# STM32_microcontroller_IOs.net
KiCad netlist of a schematic drawn in Altium Designer
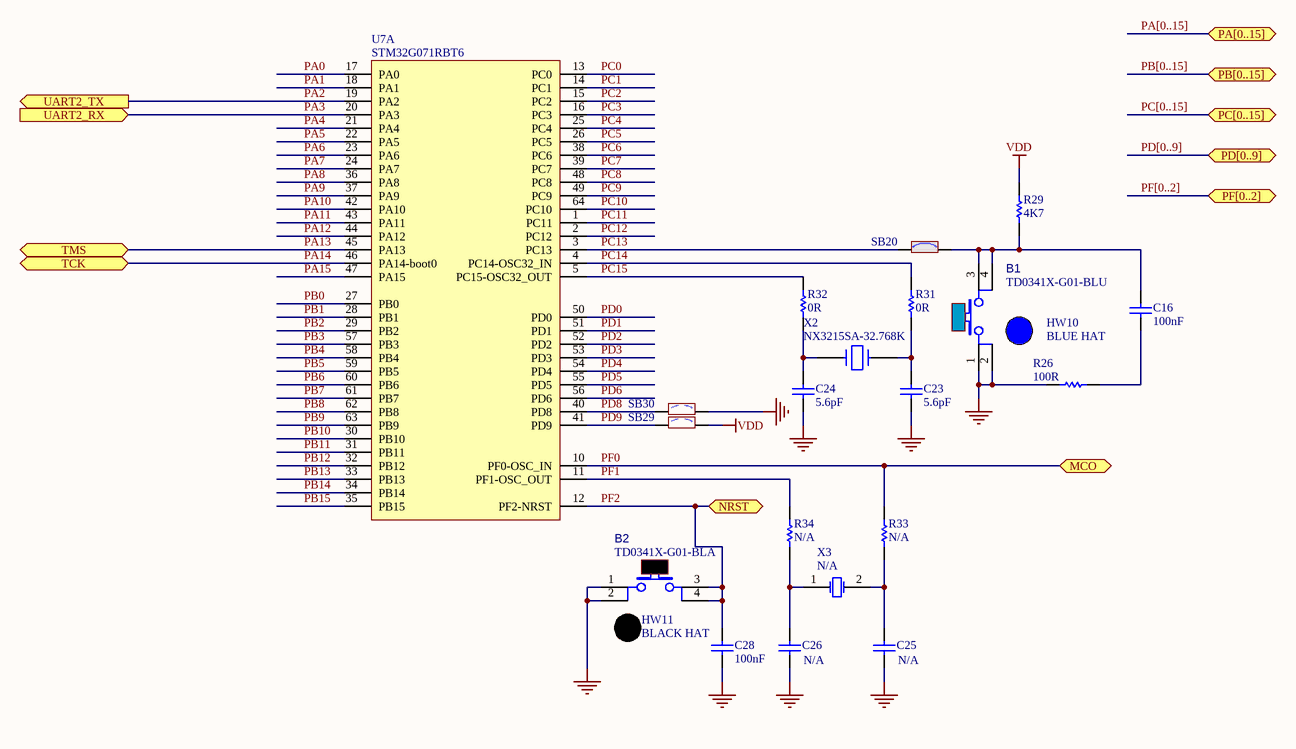
[diagram p0: STM32_microcontroller_IOs.SchDoc]

(export (version "E")
  (design (tool "Eeschema 10.0.6"))
  (components
    (comp (ref "B1")
      (value "SW-PUSH-CMS_BLUE")
      (footprint "SWI_WEALTHMETAL_TD-0341_4P_BLUE")
      (description "Non-Open Push-Button 0.1A 24V")
      (fields
        (field (name "INTERNAL_PART_NUMBER") "MCD-00002")
        (field (name "MANUFACTURER_PART_NUMBER") "TD0341X-G01-BLU")
        (field (name "MANUFACTURER") "WEALTHMETAL")
        (field (name "PROVIDED_BY") "Subcon")
      )
      (libsource (lib "MCD_PARTS_database") (part "SW-PUSH-CMS_BLUE"))
    )
    (comp (ref "B2")
      (value "SW-PUSH-CMS_BLACK")
      (footprint "SWI_WEALTHMETAL_TD-0341_4P_BLACK")
      (description "Non-Open Push-Button 0.1A 24V")
      (fields
        (field (name "INTERNAL_PART_NUMBER") "MCD-00001")
        (field (name "MANUFACTURER_PART_NUMBER") "TD0341X-G01-BLA")
        (field (name "MANUFACTURER") "WEALTHMETAL")
        (field (name "PROVIDED_BY") "Subcon")
      )
      (libsource (lib "MCD_PARTS_database") (part "SW-PUSH-CMS_BLACK"))
    )
    (comp (ref "C16")
      (value "100nF")
      (footprint "C0603")
      (description "Capacitor, MLCC, 100nF, 16V, X7R, 10%, 0603, T=0,8mm")
      (fields
        (field (name "INTERNAL_PART_NUMBER") "MCD-00211")
        (field (name "MANUFACTURER_PART_NUMBER") "CC0603KRX7R7BB104")
        (field (name "PROVIDED_BY") "Subcon")
      )
      (libsource (lib "MCD_PARTS_database") (part "Capacitor"))
    )
    (comp (ref "C23")
      (value "5.6pF")
      (footprint "C0603")
      (description "Capacitor,5.6pF,0.1pF,16V,NPO,0603")
      (fields
        (field (name "INTERNAL_PART_NUMBER") "MCD-00666")
        (field (name "MANUFACTURER_PART_NUMBER") "CC0603BRNPO7BN5R6")
        (field (name "PROVIDED_BY") "Subcon")
      )
      (libsource (lib "MCD_PARTS_database") (part "Capacitor"))
    )
    (comp (ref "C24")
      (value "5.6pF")
      (footprint "C0603")
      (description "Capacitor,5.6pF,0.1pF,16V,NPO,0603")
      (fields
        (field (name "INTERNAL_PART_NUMBER") "MCD-00666")
        (field (name "MANUFACTURER_PART_NUMBER") "CC0603BRNPO7BN5R6")
        (field (name "PROVIDED_BY") "Subcon")
      )
      (libsource (lib "MCD_PARTS_database") (part "Capacitor"))
    )
    (comp (ref "C25")
      (value "N/A")
      (footprint "C0603")
      (description "Capacitor, MLCC, 10pF, 50V, NPO, 5%, 0603, T=0,8mm")
      (fields
        (field (name "INTERNAL_PART_NUMBER") "MCD-00637")
        (field (name "MANUFACTURER_PART_NUMBER") "CC0603JRNPO9BN100")
        (field (name "PROVIDED_BY") "subcon")
      )
      (libsource (lib "MCD_PARTS_database") (part "Capacitor"))
    )
    (comp (ref "C26")
      (value "N/A")
      (footprint "C0603")
      (description "Capacitor, MLCC, 10pF, 50V, NPO, 5%, 0603, T=0,8mm")
      (fields
        (field (name "INTERNAL_PART_NUMBER") "MCD-00637")
        (field (name "MANUFACTURER_PART_NUMBER") "CC0603JRNPO9BN100")
        (field (name "PROVIDED_BY") "subcon")
      )
      (libsource (lib "MCD_PARTS_database") (part "Capacitor"))
    )
    (comp (ref "C28")
      (value "100nF")
      (footprint "C0603")
      (description "Capacitor, MLCC, 100nF, 16V, X7R, 10%, 0603, T=0,8mm")
      (fields
        (field (name "INTERNAL_PART_NUMBER") "MCD-00211")
        (field (name "MANUFACTURER_PART_NUMBER") "CC0603KRX7R7BB104")
        (field (name "PROVIDED_BY") "Subcon")
      )
      (libsource (lib "MCD_PARTS_database") (part "Capacitor"))
    )
    (comp (ref "HW10")
      (value "BLUE HAT")
      (description "Blue Hat for switch TD0341X-G01-BLU")
      (fields
        (field (name "INTERNAL_PART_NUMBER") "MCD-00634")
        (field (name "MANUFACTURER_PART_NUMBER") "988.16.09.3.00002_SH-517")
        (field (name "PROVIDED_BY") "Subcon")
      )
      (libsource (lib "MCD_PARTS_database") (part "BUTTON_HAT_BLUE"))
    )
    (comp (ref "HW11")
      (value "BLACK HAT")
      (description "Black Hat for switch TD0341X-G01-BLA")
      (fields
        (field (name "INTERNAL_PART_NUMBER") "MCD-00635")
        (field (name "MANUFACTURER_PART_NUMBER") "988.16.09.3.00003_SH-517")
        (field (name "PROVIDED_BY") "Subcon")
      )
      (libsource (lib "MCD_PARTS_database") (part "BUTTON_HAT_BLACK"))
    )
    (comp (ref "R26")
      (value "100R")
      (footprint "R0603")
      (description "Resistor,100R,0603,1%,1/10W")
      (fields
        (field (name "INTERNAL_PART_NUMBER") "MCD-00224")
        (field (name "MANUFACTURER_PART_NUMBER") "RC0603FR-07100RL")
        (field (name "PROVIDED_BY") "Subcon")
      )
      (libsource (lib "MCD_PARTS_database") (part "Resistor"))
    )
    (comp (ref "R29")
      (value "4K7")
      (footprint "R0603")
      (description "Resistor,4K7,0603,1%,1/10W")
      (fields
        (field (name "INTERNAL_PART_NUMBER") "MCD-00219")
        (field (name "MANUFACTURER_PART_NUMBER") "RC0603FR-074K7L")
        (field (name "PROVIDED_BY") "Subcon")
      )
      (libsource (lib "MCD_PARTS_database") (part "Resistor"))
    )
    (comp (ref "R31")
      (value "0R")
      (footprint "R0603")
      (description "Resistor,0R,0603,ULO")
      (fields
        (field (name "INTERNAL_PART_NUMBER") "MCD-00181")
        (field (name "MANUFACTURER_PART_NUMBER") "PMR03EZPJ000")
        (field (name "PROVIDED_BY") "Subcon")
      )
      (libsource (lib "MCD_PARTS_database") (part "Resistor"))
    )
    (comp (ref "R32")
      (value "0R")
      (footprint "R0603")
      (description "Resistor,0R,0603,ULO")
      (fields
        (field (name "INTERNAL_PART_NUMBER") "MCD-00181")
        (field (name "MANUFACTURER_PART_NUMBER") "PMR03EZPJ000")
        (field (name "PROVIDED_BY") "Subcon")
      )
      (libsource (lib "MCD_PARTS_database") (part "Resistor"))
    )
    (comp (ref "R33")
      (value "N/A")
      (footprint "R0603")
      (description "Resistor,100R,0603,1%,1/10W")
      (fields
        (field (name "INTERNAL_PART_NUMBER") "MCD-00224")
        (field (name "MANUFACTURER_PART_NUMBER") "RC0603FR-07100RL")
        (field (name "PROVIDED_BY") "Subcon")
      )
      (libsource (lib "MCD_PARTS_database") (part "Resistor"))
    )
    (comp (ref "R34")
      (value "N/A")
      (footprint "R0603")
      (description "Resistor,100R,0603,1%,1/10W")
      (fields
        (field (name "INTERNAL_PART_NUMBER") "MCD-00224")
        (field (name "MANUFACTURER_PART_NUMBER") "RC0603FR-07100RL")
        (field (name "PROVIDED_BY") "Subcon")
      )
      (libsource (lib "MCD_PARTS_database") (part "Resistor"))
    )
    (comp (ref "SB20")
      (value "SB_ON")
      (footprint "SOLDER-BRIDGE_R0603-0R")
      (description "Solder Bridge ON")
      (fields (field (name "INTERNAL_PART_NUMBER") "MCD-00071") (field (name "PROVIDED_BY") "Subcon"))
      (libsource (lib "MCD_PARTS_database") (part "SB_ON"))
    )
    (comp (ref "SB29")
      (value "SB_OFF")
      (footprint "SOLDER-BRIDGE_R0603-0R")
      (description "Solder Bridge OFF")
      (fields (field (name "INTERNAL_PART_NUMBER") "MCD-00072"))
      (libsource (lib "MCD_PARTS_database") (part "SB_OFF"))
    )
    (comp (ref "SB30")
      (value "SB_OFF")
      (footprint "SOLDER-BRIDGE_R0603-0R")
      (description "Solder Bridge OFF")
      (fields (field (name "INTERNAL_PART_NUMBER") "MCD-00072"))
      (libsource (lib "MCD_PARTS_database") (part "SB_OFF"))
    )
    (comp (ref "U7")
      (value "STM32G071RBT6")
      (footprint "ICC_LQFP64_10X10_P050_SOCKET_YAMAICHI_IC149-064-069-B5")
      (description "Medium-density performance line ARM-based 32-bit MCU with 128KB Flash")
      (fields
        (field (name "INTERNAL_PART_NUMBER") "MCD-00662")
        (field (name "MANUFACTURER") "STMICROELECTRONICS")
        (field (name "PROVIDED_BY") "STM")
      )
      (libsource (lib "MCD_PARTS_database") (part "STM32G071RBT6"))
    )
    (comp (ref "X2")
      (value "NX3215SA-32.768K")
      (footprint "CRY_NX3215SA_2P")
      (description "Crystal 32.768kHz, 6pF, -+20PPM, R=50K, SMD")
      (fields
        (field (name "INTERNAL_PART_NUMBER") "MCD-00091")
        (field (name "MANUFACTURER_PART_NUMBER") "NX3215SA 32.768KHz EXS00A-MU00525")
        (field (name "PROVIDED_BY") "STM")
      )
      (libsource (lib "MCD_PARTS_database") (part "XTAL_32K_NX3215SA"))
    )
    (comp (ref "X3")
      (value "N/A")
      (footprint "CRY_NX3225GD_2P")
      (description "Crystal 8Mhz, 8pF, -+50PPM, SMD")
      (fields
        (field (name "INTERNAL_PART_NUMBER") "MCD-00092")
        (field (name "MANUFACTURER_PART_NUMBER") "NX3225GD 8MHz EXS00A-CG04874")
        (field (name "PROVIDED_BY") "STM")
      )
      (libsource (lib "MCD_PARTS_database") (part "XTAL_8M_NX3225GD"))
    )
  )
  (nets
    (net (code "2") (name "/PA0") (class "Default")
      (node (ref "U7") (pin "17") (pinfunction "PA0_17") (pintype "passive"))
    )
    (net (code "3") (name "/PA1") (class "Default")
      (node (ref "U7") (pin "18") (pinfunction "PA1_18") (pintype "passive"))
    )
    (net (code "4") (name "/PA2") (class "Default")
      (node (ref "U7") (pin "19") (pinfunction "PA2_19") (pintype "passive"))
    )
    (net (code "5") (name "/PA3") (class "Default")
      (node (ref "U7") (pin "20") (pinfunction "PA3_20") (pintype "passive"))
    )
    (net (code "6") (name "/PA4") (class "Default")
      (node (ref "U7") (pin "21") (pinfunction "PA4_21") (pintype "passive"))
    )
    (net (code "7") (name "/PA5") (class "Default")
      (node (ref "U7") (pin "22") (pinfunction "PA5_22") (pintype "passive"))
    )
    (net (code "8") (name "/PA6") (class "Default")
      (node (ref "U7") (pin "23") (pinfunction "PA6_23") (pintype "passive"))
    )
    (net (code "9") (name "/PA7") (class "Default")
      (node (ref "U7") (pin "24") (pinfunction "PA7_24") (pintype "passive"))
    )
    (net (code "10") (name "/PA8") (class "Default")
      (node (ref "U7") (pin "36") (pinfunction "PA8_36") (pintype "passive"))
    )
    (net (code "11") (name "/PA9") (class "Default")
      (node (ref "U7") (pin "37") (pinfunction "PA9_37") (pintype "passive"))
    )
    (net (code "12") (name "/PA10") (class "Default")
      (node (ref "U7") (pin "42") (pinfunction "PA10_42") (pintype "passive"))
    )
    (net (code "13") (name "/PA11") (class "Default")
      (node (ref "U7") (pin "43") (pinfunction "PA11_43") (pintype "passive"))
    )
    (net (code "14") (name "/PA12") (class "Default")
      (node (ref "U7") (pin "44") (pinfunction "PA12_44") (pintype "passive"))
    )
    (net (code "15") (name "/PA13") (class "Default")
      (node (ref "U7") (pin "45") (pinfunction "PA13_45") (pintype "passive"))
    )
    (net (code "16") (name "/PA14") (class "Default")
      (node (ref "U7") (pin "46") (pinfunction "PA14-boot0_46") (pintype "passive"))
    )
    (net (code "17") (name "/PA15") (class "Default")
      (node (ref "U7") (pin "47") (pinfunction "PA15_47") (pintype "passive"))
    )
    (net (code "19") (name "/PB0") (class "Default")
      (node (ref "U7") (pin "27") (pinfunction "PB0_27") (pintype "passive"))
    )
    (net (code "20") (name "/PB1") (class "Default")
      (node (ref "U7") (pin "28") (pinfunction "PB1_28") (pintype "passive"))
    )
    (net (code "21") (name "/PB2") (class "Default")
      (node (ref "U7") (pin "29") (pinfunction "PB2_29") (pintype "passive"))
    )
    (net (code "22") (name "/PB3") (class "Default")
      (node (ref "U7") (pin "57") (pinfunction "PB3_57") (pintype "passive"))
    )
    (net (code "23") (name "/PB4") (class "Default")
      (node (ref "U7") (pin "58") (pinfunction "PB4_58") (pintype "passive"))
    )
    (net (code "24") (name "/PB5") (class "Default")
      (node (ref "U7") (pin "59") (pinfunction "PB5_59") (pintype "passive"))
    )
    (net (code "25") (name "/PB6") (class "Default")
      (node (ref "U7") (pin "60") (pinfunction "PB6_60") (pintype "passive"))
    )
    (net (code "26") (name "/PB7") (class "Default")
      (node (ref "U7") (pin "61") (pinfunction "PB7_61") (pintype "passive"))
    )
    (net (code "27") (name "/PB8") (class "Default")
      (node (ref "U7") (pin "62") (pinfunction "PB8_62") (pintype "passive"))
    )
    (net (code "28") (name "/PB9") (class "Default")
      (node (ref "U7") (pin "63") (pinfunction "PB9_63") (pintype "passive"))
    )
    (net (code "29") (name "/PB10") (class "Default")
      (node (ref "U7") (pin "30") (pinfunction "PB10_30") (pintype "passive"))
    )
    (net (code "30") (name "/PB11") (class "Default")
      (node (ref "U7") (pin "31") (pinfunction "PB11_31") (pintype "passive"))
    )
    (net (code "31") (name "/PB12") (class "Default")
      (node (ref "U7") (pin "32") (pinfunction "PB12_32") (pintype "passive"))
    )
    (net (code "32") (name "/PB13") (class "Default")
      (node (ref "U7") (pin "33") (pinfunction "PB13_33") (pintype "passive"))
    )
    (net (code "33") (name "/PB14") (class "Default")
      (node (ref "U7") (pin "34") (pinfunction "PB14_34") (pintype "passive"))
    )
    (net (code "34") (name "/PB15") (class "Default")
      (node (ref "U7") (pin "35") (pinfunction "PB15_35") (pintype "passive"))
    )
    (net (code "36") (name "/PC0") (class "Default")
      (node (ref "U7") (pin "13") (pinfunction "PC0_13") (pintype "passive"))
    )
    (net (code "37") (name "/PC1") (class "Default")
      (node (ref "U7") (pin "14") (pinfunction "PC1_14") (pintype "passive"))
    )
    (net (code "38") (name "/PC2") (class "Default")
      (node (ref "U7") (pin "15") (pinfunction "PC2_15") (pintype "passive"))
    )
    (net (code "39") (name "/PC3") (class "Default")
      (node (ref "U7") (pin "16") (pinfunction "PC3_16") (pintype "passive"))
    )
    (net (code "40") (name "/PC4") (class "Default")
      (node (ref "U7") (pin "25") (pinfunction "PC4_25") (pintype "passive"))
    )
    (net (code "41") (name "/PC5") (class "Default")
      (node (ref "U7") (pin "26") (pinfunction "PC5_26") (pintype "passive"))
    )
    (net (code "42") (name "/PC6") (class "Default")
      (node (ref "U7") (pin "38") (pinfunction "PC6_38") (pintype "passive"))
    )
    (net (code "43") (name "/PC7") (class "Default")
      (node (ref "U7") (pin "39") (pinfunction "PC7_39") (pintype "passive"))
    )
    (net (code "44") (name "/PC8") (class "Default")
      (node (ref "U7") (pin "48") (pinfunction "PC8_48") (pintype "passive"))
    )
    (net (code "45") (name "/PC9") (class "Default")
      (node (ref "U7") (pin "49") (pinfunction "PC9_49") (pintype "passive"))
    )
    (net (code "46") (name "/PC10") (class "Default")
      (node (ref "U7") (pin "64") (pinfunction "PC10_64") (pintype "passive"))
    )
    (net (code "47") (name "/PC11") (class "Default")
      (node (ref "U7") (pin "1") (pinfunction "PC11_1") (pintype "passive"))
    )
    (net (code "48") (name "/PC12") (class "Default")
      (node (ref "U7") (pin "2") (pinfunction "PC12_2") (pintype "passive"))
    )
    (net (code "49") (name "/PC13") (class "Default")
      (node (ref "SB20") (pin "1") (pinfunction "1_1") (pintype "passive"))
      (node (ref "U7") (pin "3") (pinfunction "PC13_3") (pintype "passive"))
    )
    (net (code "50") (name "/PC14") (class "Default")
      (node (ref "R31") (pin "1") (pinfunction "1_1") (pintype "passive"))
      (node (ref "U7") (pin "4") (pinfunction "PC14-OSC32_IN_4") (pintype "passive"))
    )
    (net (code "51") (name "/PC15") (class "Default")
      (node (ref "R32") (pin "1") (pinfunction "1_1") (pintype "passive"))
      (node (ref "U7") (pin "5") (pinfunction "PC15-OSC32_OUT_5") (pintype "passive"))
    )
    (net (code "53") (name "/PD0") (class "Default")
      (node (ref "U7") (pin "50") (pinfunction "PD0_50") (pintype "passive"))
    )
    (net (code "54") (name "/PD1") (class "Default")
      (node (ref "U7") (pin "51") (pinfunction "PD1_51") (pintype "passive"))
    )
    (net (code "55") (name "/PD2") (class "Default")
      (node (ref "U7") (pin "52") (pinfunction "PD2_52") (pintype "passive"))
    )
    (net (code "56") (name "/PD3") (class "Default")
      (node (ref "U7") (pin "53") (pinfunction "PD3_53") (pintype "passive"))
    )
    (net (code "57") (name "/PD4") (class "Default")
      (node (ref "U7") (pin "54") (pinfunction "PD4_54") (pintype "passive"))
    )
    (net (code "58") (name "/PD5") (class "Default")
      (node (ref "U7") (pin "55") (pinfunction "PD5_55") (pintype "passive"))
    )
    (net (code "59") (name "/PD6") (class "Default")
      (node (ref "U7") (pin "56") (pinfunction "PD6_56") (pintype "passive"))
    )
    (net (code "60") (name "/PD8") (class "Default")
      (node (ref "SB30") (pin "1") (pinfunction "1_1") (pintype "passive"))
      (node (ref "U7") (pin "40") (pinfunction "PD8_40") (pintype "passive"))
    )
    (net (code "61") (name "/PD9") (class "Default")
      (node (ref "SB29") (pin "1") (pinfunction "1_1") (pintype "passive"))
      (node (ref "U7") (pin "41") (pinfunction "PD9_41") (pintype "passive"))
    )
    (net (code "63") (name "/PF0") (class "Default")
      (node (ref "R33") (pin "1") (pinfunction "1_1") (pintype "passive"))
      (node (ref "U7") (pin "10") (pinfunction "PF0-OSC_IN_10") (pintype "passive"))
    )
    (net (code "64") (name "/PF1") (class "Default")
      (node (ref "R34") (pin "1") (pinfunction "1_1") (pintype "passive"))
      (node (ref "U7") (pin "11") (pinfunction "PF1-OSC_OUT_11") (pintype "passive"))
    )
    (net (code "65") (name "/PF2") (class "Default")
      (node (ref "B2") (pin "3") (pinfunction "3_3") (pintype "passive"))
      (node (ref "B2") (pin "4") (pinfunction "4_4") (pintype "passive"))
      (node (ref "C28") (pin "2") (pinfunction "2_2") (pintype "passive"))
      (node (ref "U7") (pin "12") (pinfunction "PF2-NRST_12") (pintype "passive"))
    )
    (net (code "67") (name "GND") (class "Default")
      (node (ref "B1") (pin "1") (pinfunction "1_1") (pintype "passive"))
      (node (ref "B1") (pin "2") (pinfunction "2_2") (pintype "passive"))
      (node (ref "B2") (pin "1") (pinfunction "1_1") (pintype "passive"))
      (node (ref "B2") (pin "2") (pinfunction "2_2") (pintype "passive"))
      (node (ref "C23") (pin "1") (pinfunction "1_1") (pintype "passive"))
      (node (ref "C24") (pin "1") (pinfunction "1_1") (pintype "passive"))
      (node (ref "C25") (pin "1") (pinfunction "1_1") (pintype "passive"))
      (node (ref "C26") (pin "1") (pinfunction "1_1") (pintype "passive"))
      (node (ref "C28") (pin "1") (pinfunction "1_1") (pintype "passive"))
      (node (ref "R26") (pin "1") (pinfunction "1_1") (pintype "passive"))
      (node (ref "SB30") (pin "2") (pinfunction "2_2") (pintype "passive"))
    )
    (net (code "68") (name "Net-(B1-Pad3)") (class "Default")
      (node (ref "B1") (pin "3") (pinfunction "3_3") (pintype "passive"))
      (node (ref "B1") (pin "4") (pinfunction "4_4") (pintype "passive"))
      (node (ref "C16") (pin "2") (pinfunction "2_2") (pintype "passive"))
      (node (ref "R29") (pin "1") (pinfunction "1_1") (pintype "passive"))
      (node (ref "SB20") (pin "2") (pinfunction "2_2") (pintype "passive"))
    )
    (net (code "69") (name "Net-(C16-Pad1)") (class "Default")
      (node (ref "C16") (pin "1") (pinfunction "1_1") (pintype "passive"))
      (node (ref "R26") (pin "2") (pinfunction "2_2") (pintype "passive"))
    )
    (net (code "70") (name "Net-(C23-Pad2)") (class "Default")
      (node (ref "C23") (pin "2") (pinfunction "2_2") (pintype "passive"))
      (node (ref "R31") (pin "2") (pinfunction "2_2") (pintype "passive"))
      (node (ref "X2") (pin "2") (pinfunction "2_2") (pintype "passive"))
    )
    (net (code "71") (name "Net-(C24-Pad2)") (class "Default")
      (node (ref "C24") (pin "2") (pinfunction "2_2") (pintype "passive"))
      (node (ref "R32") (pin "2") (pinfunction "2_2") (pintype "passive"))
      (node (ref "X2") (pin "1") (pinfunction "1_1") (pintype "passive"))
    )
    (net (code "72") (name "Net-(X3-OSC1)") (class "Default")
      (node (ref "C26") (pin "2") (pinfunction "2_2") (pintype "passive"))
      (node (ref "R34") (pin "2") (pinfunction "2_2") (pintype "passive"))
      (node (ref "X3") (pin "1") (pinfunction "OSC1_1") (pintype "passive"))
    )
    (net (code "73") (name "Net-(X3-OSC2)") (class "Default")
      (node (ref "C25") (pin "2") (pinfunction "2_2") (pintype "passive"))
      (node (ref "R33") (pin "2") (pinfunction "2_2") (pintype "passive"))
      (node (ref "X3") (pin "2") (pinfunction "OSC2_2") (pintype "passive"))
    )
    (net (code "74") (name "VDD") (class "Default")
      (node (ref "R29") (pin "2") (pinfunction "2_2") (pintype "passive"))
      (node (ref "SB29") (pin "2") (pinfunction "2_2") (pintype "passive"))
    )
  )
)
